# USE_C.net
KiCad netlist of a schematic drawn in Altium Designer
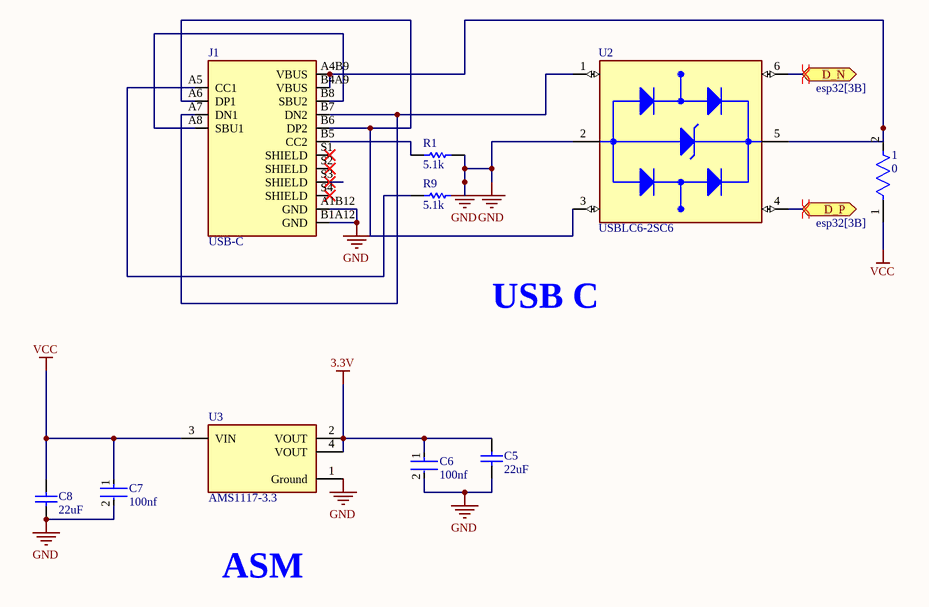
[diagram p0: USE C.SchDoc]

(export (version "E")
  (design (tool "Eeschema 10.0.6"))
  (components
    (comp (ref "1")
      (value "0")
      (footprint "FP-RC0402-0_4-IPC_A")
      (description "RES SMD 0 OHM JUMPER 1/16W 0402")
      (fields (field (name "TOLERANCE") "1%"))
      (libsource (lib "Altium Content Vault") (part "1029c3af85768c4190bb7ad29bc67b5"))
    )
    (comp (ref "C5")
      (value "22uF")
      (footprint "CAPC3216X180X55ML20T25")
      (description "Chip Capacitor, 22 uF, +/- 10%, 25 V, -55 to 85 degC, 1206 (3216 Metric), RoHS, Tape and Reel")
      (fields (field (name "PARTNUMBER") "GRM31CR61E226KE15L") (field (name "TOLERANCE") "10%"))
      (libsource (lib "Altium Content Vault") (part "CAP-NP-2"))
    )
    (comp (ref "C6")
      (value "100nf")
      (footprint "FP-CC0603-DA-MFG")
      (description "CAP CER 0.1UF 50V X7R 0603")
      (fields (field (name "MANUFACTURER") "YAGEO") (field (name "VOLTAGE") "50 V"))
      (libsource (lib "Altium Content Vault") (part "11868f565c42a9108669ba33697ecf6"))
    )
    (comp (ref "C7")
      (value "100nf")
      (footprint "FP-CC0603-DA-MFG")
      (description "CAP CER 0.1UF 50V X7R 0603")
      (fields (field (name "MANUFACTURER") "YAGEO") (field (name "VOLTAGE") "50 V"))
      (libsource (lib "Altium Content Vault") (part "11868f565c42a9108669ba33697ecf6"))
    )
    (comp (ref "C8")
      (value "22uF")
      (footprint "CAPC3216X180X55ML20T25")
      (description "Chip Capacitor, 22 uF, +/- 10%, 25 V, -55 to 85 degC, 1206 (3216 Metric), RoHS, Tape and Reel")
      (fields (field (name "PARTNUMBER") "GRM31CR61E226KE15L") (field (name "TOLERANCE") "10%"))
      (libsource (lib "Altium Content Vault") (part "CAP-NP-2"))
    )
    (comp (ref "J1")
      (value "USB-C")
      (footprint "HRO_TYPE-C-31-M-12")
      (fields (field (name "MF") "Adam Technologies"))
      (libsource (lib "USB-C") (part "USB-C"))
    )
    (comp (ref "R1")
      (value "5.1k")
      (footprint "RESC1005X40X25NL05T10")
      (fields (field (name "PART NUMBER") "RC0402FR-075K1L") (field (name "MANUFACTURER") "Yageo / Phycomp"))
      (libsource (lib "Altium Content Vault") (part "RES"))
    )
    (comp (ref "R9")
      (value "5.1k")
      (footprint "RESC1005X40X25NL05T10")
      (fields (field (name "PART NUMBER") "RC0402FR-075K1L") (field (name "MANUFACTURER") "Yageo / Phycomp"))
      (libsource (lib "Altium Content Vault") (part "RES"))
    )
    (comp (ref "U2")
      (value "USBLC6-2SC6")
      (footprint "SOT95P280X145-6N")
      (description "17V Clamp 5A (8/20Âµs) Ipp Tvs Diode Surface Mount SOT-23-6")
      (fields (field (name "MF") "STMicroelectronics"))
      (libsource (lib "USBLC6-2SC6") (part "USBLC6-2SC6"))
    )
    (comp (ref "U3")
      (value "AMS1117-3.3")
      (footprint "FP-AMS1117-IPC_C")
      (description "LDO Voltage Regulators 1A, 3.3V")
      (fields
        (field (name "OCTOPART") "https://octopart.com/ams1117-3.3-advanced+monolithic+systems-25899300")
        (field (name "MANUFACTURER") "Advanced Monolithic Systems")
      )
      (libsource (lib "Altium Content Vault") (part "8bdbb5f8e77002000e30dd2845d0354"))
    )
  )
  (nets
    (net (code "1") (name "/D_N") (class "Default")
      (node (ref "U2") (pin "6") (pinfunction "I/O1_OUT_6") (pintype "bidirectional"))
    )
    (net (code "2") (name "/D_P") (class "Default")
      (node (ref "U2") (pin "4") (pinfunction "I/O2_OUT_4") (pintype "bidirectional"))
    )
    (net (code "3") (name "3.3V") (class "Default")
      (node (ref "C5") (pin "2") (pinfunction "2_2") (pintype "passive"))
      (node (ref "C6") (pin "1") (pinfunction "1_1") (pintype "passive"))
      (node (ref "U3") (pin "2") (pinfunction "VOUT_2") (pintype "passive"))
      (node (ref "U3") (pin "4") (pinfunction "VOUT_4") (pintype "passive"))
    )
    (net (code "4") (name "GND") (class "Default")
      (node (ref "C5") (pin "1") (pinfunction "1_1") (pintype "passive"))
      (node (ref "C6") (pin "2") (pinfunction "2_2") (pintype "passive"))
      (node (ref "C7") (pin "2") (pinfunction "2_2") (pintype "passive"))
      (node (ref "C8") (pin "1") (pinfunction "1_1") (pintype "passive"))
      (node (ref "J1") (pin "A1B12") (pinfunction "GND_A1B12") (pintype "power_in"))
      (node (ref "J1") (pin "B1A12") (pinfunction "GND_B1A12") (pintype "power_in"))
      (node (ref "R1") (pin "2") (pinfunction "2_2") (pintype "passive"))
      (node (ref "R9") (pin "2") (pinfunction "2_2") (pintype "passive"))
      (node (ref "U2") (pin "2") (pinfunction "GND_2") (pintype "power_in"))
      (node (ref "U3") (pin "1") (pinfunction "Ground_1") (pintype "power_in"))
    )
    (net (code "5") (name "Net-(J1-CC1)") (class "Default")
      (node (ref "J1") (pin "A5") (pinfunction "CC1_A5") (pintype "bidirectional"))
      (node (ref "R9") (pin "1") (pinfunction "1_1") (pintype "passive"))
    )
    (net (code "6") (name "Net-(J1-CC2)") (class "Default")
      (node (ref "J1") (pin "B5") (pinfunction "CC2_B5") (pintype "bidirectional"))
      (node (ref "R1") (pin "1") (pinfunction "1_1") (pintype "passive"))
    )
    (net (code "7") (name "Net-(J1-DN1)") (class "Default")
      (node (ref "J1") (pin "A7") (pinfunction "DN1_A7") (pintype "bidirectional"))
      (node (ref "J1") (pin "B7") (pinfunction "DN2_B7") (pintype "bidirectional"))
      (node (ref "U2") (pin "1") (pinfunction "I/O1_IN_1") (pintype "bidirectional"))
    )
    (net (code "8") (name "Net-(J1-DP1)") (class "Default")
      (node (ref "J1") (pin "A6") (pinfunction "DP1_A6") (pintype "bidirectional"))
      (node (ref "J1") (pin "B6") (pinfunction "DP2_B6") (pintype "bidirectional"))
      (node (ref "U2") (pin "3") (pinfunction "I/O2_IN_3") (pintype "bidirectional"))
    )
    (net (code "9") (name "Net-(J1-SBU1)") (class "Default")
      (node (ref "J1") (pin "A8") (pinfunction "SBU1_A8") (pintype "bidirectional"))
      (node (ref "J1") (pin "B8") (pinfunction "SBU2_B8") (pintype "bidirectional"))
    )
    (net (code "10") (name "Net-(U2-VBUS)") (class "Default")
      (node (ref "1") (pin "2") (pinfunction "2_2") (pintype "passive"))
      (node (ref "J1") (pin "A4B9") (pinfunction "VBUS_A4B9") (pintype "power_in"))
      (node (ref "J1") (pin "B4A9") (pinfunction "VBUS_B4A9") (pintype "power_in"))
      (node (ref "U2") (pin "5") (pinfunction "VBUS_5") (pintype "power_in"))
    )
    (net (code "11") (name "VCC") (class "Default")
      (node (ref "1") (pin "1") (pinfunction "1_1") (pintype "passive"))
      (node (ref "C7") (pin "1") (pinfunction "1_1") (pintype "passive"))
      (node (ref "C8") (pin "2") (pinfunction "2_2") (pintype "passive"))
      (node (ref "U3") (pin "3") (pinfunction "VIN_3") (pintype "power_in"))
    )
    (net (code "12") (name "unconnected-(J1-SHIELD-PadS1)") (class "Default")
      (node (ref "J1") (pin "S1") (pinfunction "SHIELD_S1") (pintype "passive+no_connect"))
    )
    (net (code "13") (name "unconnected-(J1-SHIELD-PadS2)") (class "Default")
      (node (ref "J1") (pin "S2") (pinfunction "SHIELD_S2") (pintype "passive+no_connect"))
    )
    (net (code "14") (name "unconnected-(J1-SHIELD-PadS3)") (class "Default")
      (node (ref "J1") (pin "S3") (pinfunction "SHIELD_S3") (pintype "passive+no_connect"))
    )
    (net (code "15") (name "unconnected-(J1-SHIELD-PadS4)") (class "Default")
      (node (ref "J1") (pin "S4") (pinfunction "SHIELD_S4") (pintype "passive+no_connect"))
    )
  )
)
